# LIDO-HW_200_MCU_Peripherals_1.net
KiCad netlist of a schematic drawn in Altium Designer
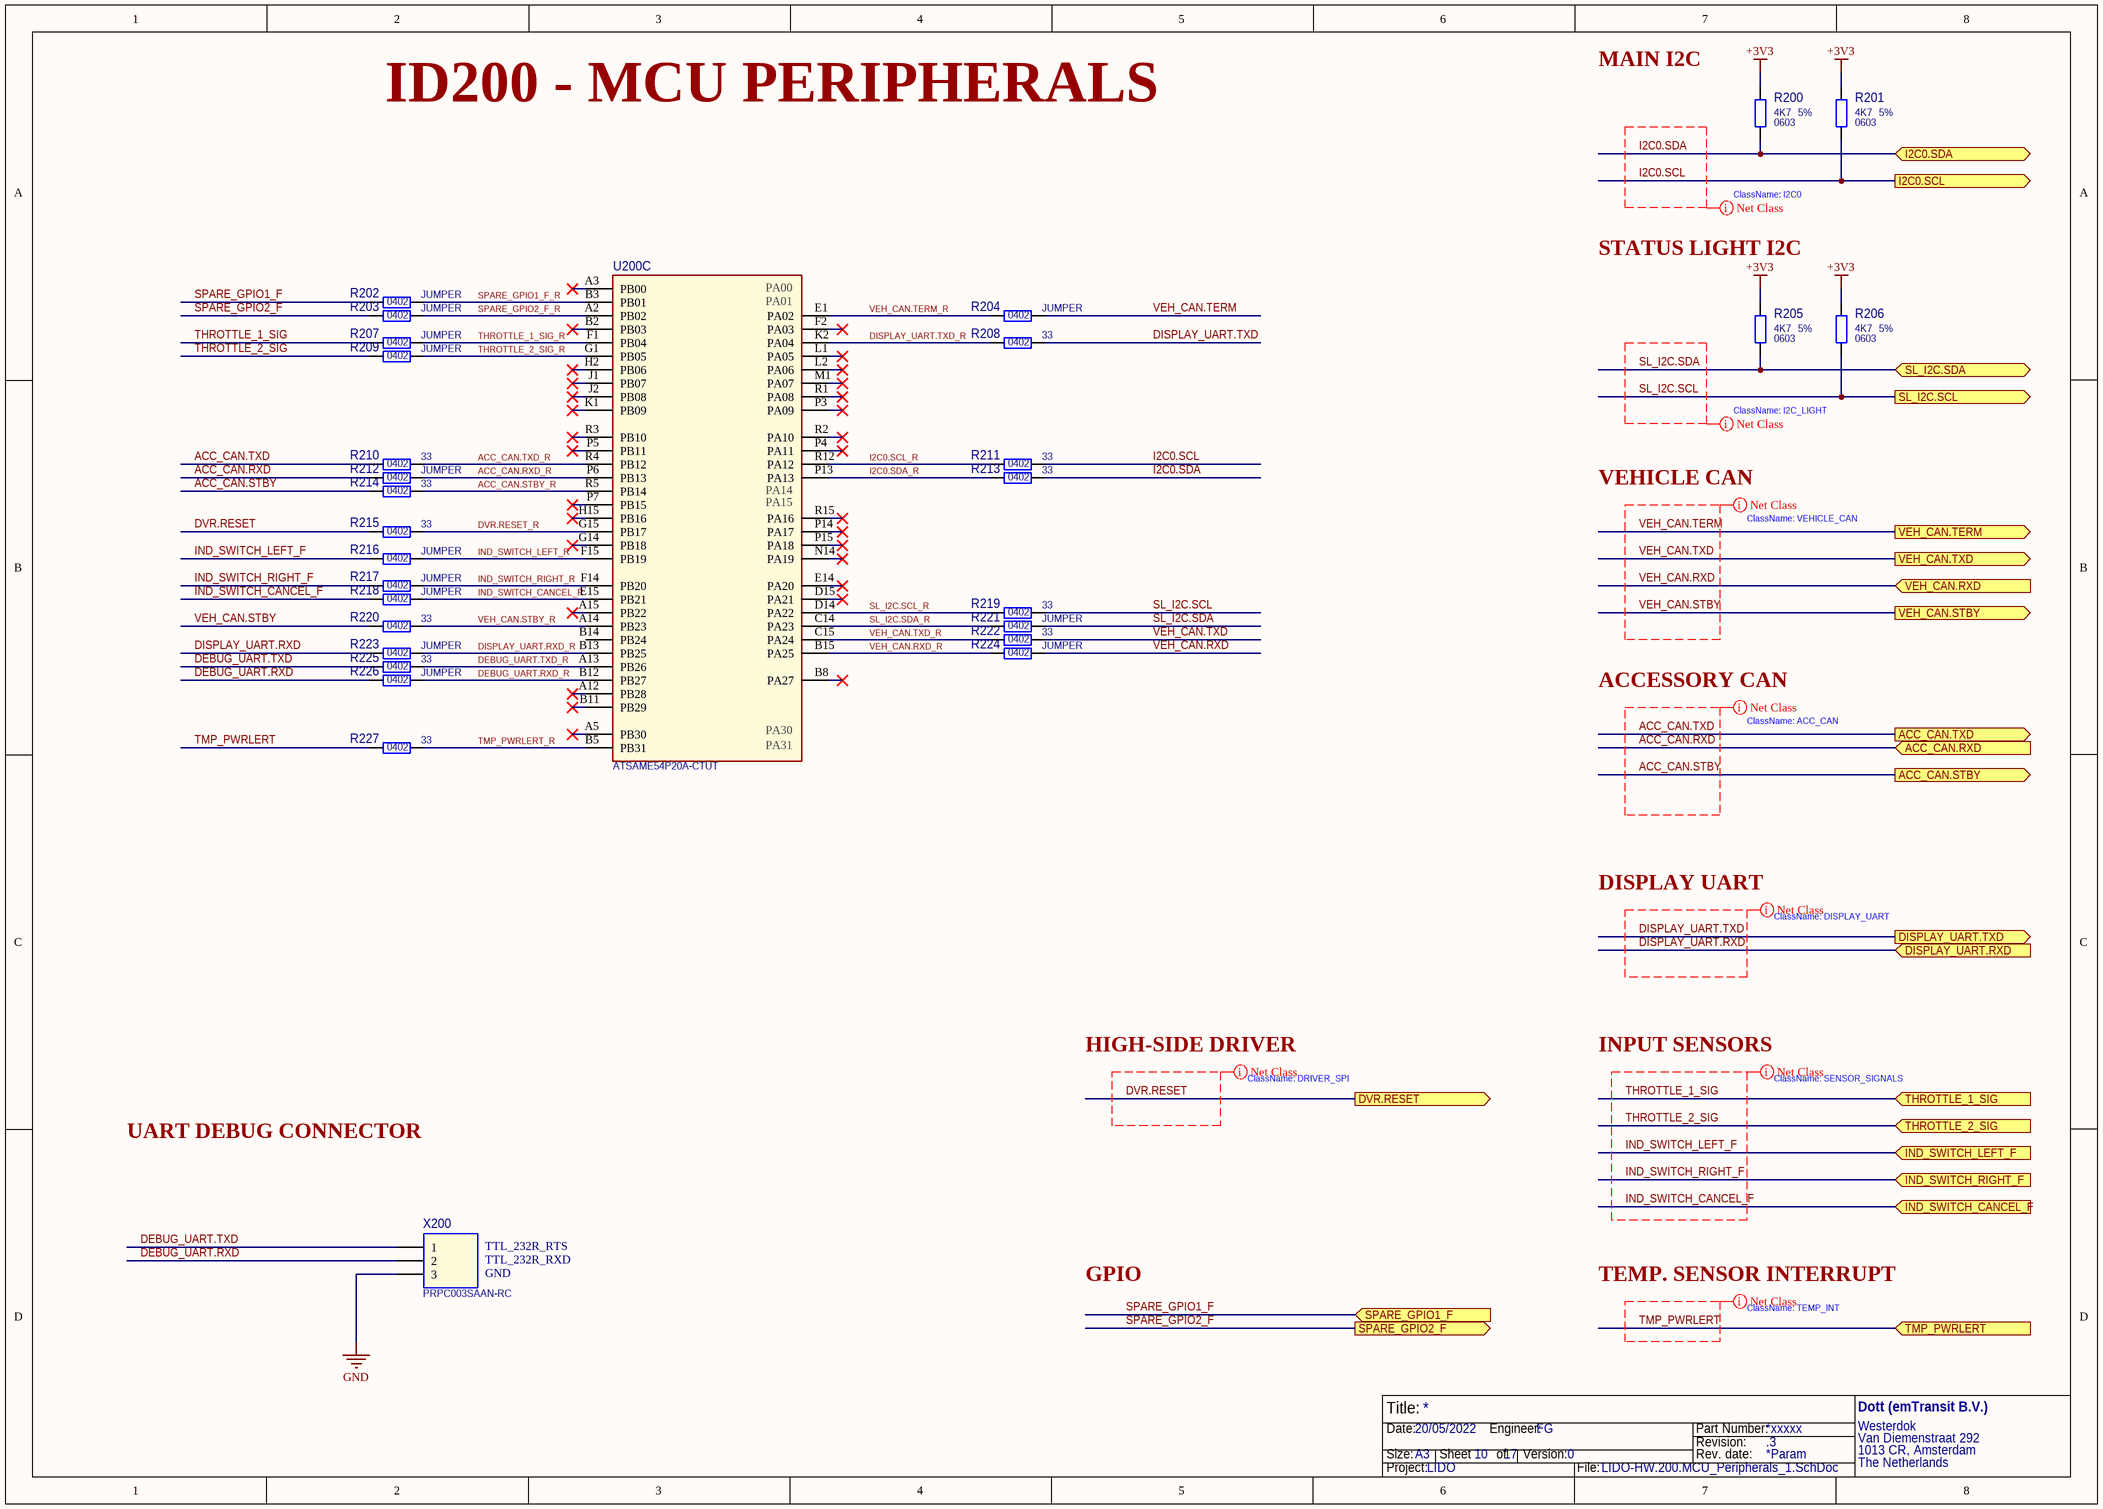
[diagram p0: LIDO-HW.200.MCU_Peripherals_1.SchDoc]

(export (version "E")
  (design (tool "Eeschema 10.0.6"))
  (components
    (comp (ref "R200")
      (value "4K7")
      (footprint "RES_0603_1608X60-N_YAGEO_A")
      (description "RES 4.7K OHM 5% 1/10W 0603")
      (fields
        (field (name "MANUFACTURER PART NUMBER") "RC0603JR-074K7L")
        (field (name "MANUFACTURER") "YAGEO")
        (field (name "PART VALUE 2") "5%")
        (field (name "PART PACKAGE") "0603")
      )
      (libsource (lib "") (part "Resistor_1"))
    )
    (comp (ref "R201")
      (value "4K7")
      (footprint "RES_0603_1608X60-N_YAGEO_A")
      (description "RES 4.7K OHM 5% 1/10W 0603")
      (fields
        (field (name "MANUFACTURER PART NUMBER") "RC0603JR-074K7L")
        (field (name "MANUFACTURER") "YAGEO")
        (field (name "PART VALUE 2") "5%")
        (field (name "PART PACKAGE") "0603")
      )
      (libsource (lib "") (part "Resistor_1"))
    )
    (comp (ref "R202")
      (value "JUMPER")
      (footprint "RES_0402_1005X40-N_YAGEO_A")
      (description "RES SMD 0 OHM JUMPER 1/10W 0402")
      (fields
        (field (name "MANUFACTURER PART NUMBER") "ERJ-2GE0R00X")
        (field (name "MANUFACTURER") "Panasonic Electronic Components")
        (field (name "PART PACKAGE") "0402")
      )
      (libsource (lib "DB_Library") (part "Resistor"))
    )
    (comp (ref "R203")
      (value "JUMPER")
      (footprint "RES_0402_1005X40-N_YAGEO_A")
      (description "RES SMD 0 OHM JUMPER 1/10W 0402")
      (fields
        (field (name "MANUFACTURER PART NUMBER") "ERJ-2GE0R00X")
        (field (name "MANUFACTURER") "Panasonic Electronic Components")
        (field (name "PART PACKAGE") "0402")
      )
      (libsource (lib "DB_Library") (part "Resistor"))
    )
    (comp (ref "R204")
      (value "JUMPER")
      (footprint "RES_0402_1005X40-N_YAGEO_A")
      (description "RES SMD 0 OHM JUMPER 1/10W 0402")
      (fields
        (field (name "MANUFACTURER PART NUMBER") "ERJ-2GE0R00X")
        (field (name "MANUFACTURER") "Panasonic Electronic Components")
        (field (name "PART PACKAGE") "0402")
      )
      (libsource (lib "DB_Library") (part "Resistor"))
    )
    (comp (ref "R205")
      (value "4K7")
      (footprint "RES_0603_1608X60-N_YAGEO_A")
      (description "RES 4.7K OHM 5% 1/10W 0603")
      (fields
        (field (name "MANUFACTURER PART NUMBER") "RC0603JR-074K7L")
        (field (name "MANUFACTURER") "YAGEO")
        (field (name "PART VALUE 2") "5%")
        (field (name "PART PACKAGE") "0603")
      )
      (libsource (lib "") (part "Resistor_1"))
    )
    (comp (ref "R206")
      (value "4K7")
      (footprint "RES_0603_1608X60-N_YAGEO_A")
      (description "RES 4.7K OHM 5% 1/10W 0603")
      (fields
        (field (name "MANUFACTURER PART NUMBER") "RC0603JR-074K7L")
        (field (name "MANUFACTURER") "YAGEO")
        (field (name "PART VALUE 2") "5%")
        (field (name "PART PACKAGE") "0603")
      )
      (libsource (lib "") (part "Resistor_1"))
    )
    (comp (ref "R207")
      (value "JUMPER")
      (footprint "RES_0402_1005X40-N_YAGEO_A")
      (description "RES SMD 0 OHM JUMPER 1/10W 0402")
      (fields
        (field (name "MANUFACTURER PART NUMBER") "ERJ-2GE0R00X")
        (field (name "MANUFACTURER") "Panasonic Electronic Components")
        (field (name "PART PACKAGE") "0402")
      )
      (libsource (lib "DB_Library") (part "Resistor"))
    )
    (comp (ref "R208")
      (value "33")
      (footprint "RES_0402_1005X40-N_YAGEO_A")
      (description "RES SMD 33 OHM 5% 1/10W 0402")
      (fields
        (field (name "MANUFACTURER PART NUMBER") "ERJ-2GEJ330X")
        (field (name "MANUFACTURER") "Panasonic Electronic Components")
        (field (name "PART PACKAGE") "0402")
      )
      (libsource (lib "DB_Library") (part "Resistor"))
    )
    (comp (ref "R209")
      (value "JUMPER")
      (footprint "RES_0402_1005X40-N_YAGEO_A")
      (description "RES SMD 0 OHM JUMPER 1/10W 0402")
      (fields
        (field (name "MANUFACTURER PART NUMBER") "ERJ-2GE0R00X")
        (field (name "MANUFACTURER") "Panasonic Electronic Components")
        (field (name "PART PACKAGE") "0402")
      )
      (libsource (lib "DB_Library") (part "Resistor"))
    )
    (comp (ref "R210")
      (value "33")
      (footprint "RES_0402_1005X40-N_YAGEO_A")
      (description "RES SMD 33 OHM 5% 1/10W 0402")
      (fields
        (field (name "MANUFACTURER PART NUMBER") "ERJ-2GEJ330X")
        (field (name "MANUFACTURER") "Panasonic Electronic Components")
        (field (name "PART PACKAGE") "0402")
      )
      (libsource (lib "DB_Library") (part "Resistor"))
    )
    (comp (ref "R211")
      (value "33")
      (footprint "RES_0402_1005X40-N_YAGEO_A")
      (description "RES SMD 33 OHM 5% 1/10W 0402")
      (fields
        (field (name "MANUFACTURER PART NUMBER") "ERJ-2GEJ330X")
        (field (name "MANUFACTURER") "Panasonic Electronic Components")
        (field (name "PART PACKAGE") "0402")
      )
      (libsource (lib "DB_Library") (part "Resistor"))
    )
    (comp (ref "R212")
      (value "JUMPER")
      (footprint "RES_0402_1005X40-N_YAGEO_A")
      (description "RES SMD 0 OHM JUMPER 1/10W 0402")
      (fields
        (field (name "MANUFACTURER PART NUMBER") "ERJ-2GE0R00X")
        (field (name "MANUFACTURER") "Panasonic Electronic Components")
        (field (name "PART PACKAGE") "0402")
      )
      (libsource (lib "DB_Library") (part "Resistor"))
    )
    (comp (ref "R213")
      (value "33")
      (footprint "RES_0402_1005X40-N_YAGEO_A")
      (description "RES SMD 33 OHM 5% 1/10W 0402")
      (fields
        (field (name "MANUFACTURER PART NUMBER") "ERJ-2GEJ330X")
        (field (name "MANUFACTURER") "Panasonic Electronic Components")
        (field (name "PART PACKAGE") "0402")
      )
      (libsource (lib "DB_Library") (part "Resistor"))
    )
    (comp (ref "R214")
      (value "33")
      (footprint "RES_0402_1005X40-N_YAGEO_A")
      (description "RES SMD 33 OHM 5% 1/10W 0402")
      (fields
        (field (name "MANUFACTURER PART NUMBER") "ERJ-2GEJ330X")
        (field (name "MANUFACTURER") "Panasonic Electronic Components")
        (field (name "PART PACKAGE") "0402")
      )
      (libsource (lib "DB_Library") (part "Resistor"))
    )
    (comp (ref "R215")
      (value "33")
      (footprint "RES_0402_1005X40-N_YAGEO_A")
      (description "RES SMD 33 OHM 5% 1/10W 0402")
      (fields
        (field (name "MANUFACTURER PART NUMBER") "ERJ-2GEJ330X")
        (field (name "MANUFACTURER") "Panasonic Electronic Components")
        (field (name "PART PACKAGE") "0402")
      )
      (libsource (lib "DB_Library") (part "Resistor"))
    )
    (comp (ref "R216")
      (value "JUMPER")
      (footprint "RES_0402_1005X40-N_YAGEO_A")
      (description "RES SMD 0 OHM JUMPER 1/10W 0402")
      (fields
        (field (name "MANUFACTURER PART NUMBER") "ERJ-2GE0R00X")
        (field (name "MANUFACTURER") "Panasonic Electronic Components")
        (field (name "PART PACKAGE") "0402")
      )
      (libsource (lib "DB_Library") (part "Resistor"))
    )
    (comp (ref "R217")
      (value "JUMPER")
      (footprint "RES_0402_1005X40-N_YAGEO_A")
      (description "RES SMD 0 OHM JUMPER 1/10W 0402")
      (fields
        (field (name "MANUFACTURER PART NUMBER") "ERJ-2GE0R00X")
        (field (name "MANUFACTURER") "Panasonic Electronic Components")
        (field (name "PART PACKAGE") "0402")
      )
      (libsource (lib "DB_Library") (part "Resistor"))
    )
    (comp (ref "R218")
      (value "JUMPER")
      (footprint "RES_0402_1005X40-N_YAGEO_A")
      (description "RES SMD 0 OHM JUMPER 1/10W 0402")
      (fields
        (field (name "MANUFACTURER PART NUMBER") "ERJ-2GE0R00X")
        (field (name "MANUFACTURER") "Panasonic Electronic Components")
        (field (name "PART PACKAGE") "0402")
      )
      (libsource (lib "DB_Library") (part "Resistor"))
    )
    (comp (ref "R219")
      (value "33")
      (footprint "RES_0402_1005X40-N_YAGEO_A")
      (description "RES SMD 33 OHM 5% 1/10W 0402")
      (fields
        (field (name "MANUFACTURER PART NUMBER") "ERJ-2GEJ330X")
        (field (name "MANUFACTURER") "Panasonic Electronic Components")
        (field (name "PART PACKAGE") "0402")
      )
      (libsource (lib "DB_Library") (part "Resistor"))
    )
    (comp (ref "R220")
      (value "33")
      (footprint "RES_0402_1005X40-N_YAGEO_A")
      (description "RES SMD 33 OHM 5% 1/10W 0402")
      (fields
        (field (name "MANUFACTURER PART NUMBER") "ERJ-2GEJ330X")
        (field (name "MANUFACTURER") "Panasonic Electronic Components")
        (field (name "PART PACKAGE") "0402")
      )
      (libsource (lib "DB_Library") (part "Resistor"))
    )
    (comp (ref "R221")
      (value "JUMPER")
      (footprint "RES_0402_1005X40-N_YAGEO_A")
      (description "RES SMD 0 OHM JUMPER 1/10W 0402")
      (fields
        (field (name "MANUFACTURER PART NUMBER") "ERJ-2GE0R00X")
        (field (name "MANUFACTURER") "Panasonic Electronic Components")
        (field (name "PART PACKAGE") "0402")
      )
      (libsource (lib "DB_Library") (part "Resistor"))
    )
    (comp (ref "R222")
      (value "33")
      (footprint "RES_0402_1005X40-N_YAGEO_A")
      (description "RES SMD 33 OHM 5% 1/10W 0402")
      (fields
        (field (name "MANUFACTURER PART NUMBER") "ERJ-2GEJ330X")
        (field (name "MANUFACTURER") "Panasonic Electronic Components")
        (field (name "PART PACKAGE") "0402")
      )
      (libsource (lib "DB_Library") (part "Resistor"))
    )
    (comp (ref "R223")
      (value "JUMPER")
      (footprint "RES_0402_1005X40-N_YAGEO_A")
      (description "RES SMD 0 OHM JUMPER 1/10W 0402")
      (fields
        (field (name "MANUFACTURER PART NUMBER") "ERJ-2GE0R00X")
        (field (name "MANUFACTURER") "Panasonic Electronic Components")
        (field (name "PART PACKAGE") "0402")
      )
      (libsource (lib "DB_Library") (part "Resistor"))
    )
    (comp (ref "R224")
      (value "JUMPER")
      (footprint "RES_0402_1005X40-N_YAGEO_A")
      (description "RES SMD 0 OHM JUMPER 1/10W 0402")
      (fields
        (field (name "MANUFACTURER PART NUMBER") "ERJ-2GE0R00X")
        (field (name "MANUFACTURER") "Panasonic Electronic Components")
        (field (name "PART PACKAGE") "0402")
      )
      (libsource (lib "DB_Library") (part "Resistor"))
    )
    (comp (ref "R225")
      (value "33")
      (footprint "RES_0402_1005X40-N_YAGEO_A")
      (description "RES SMD 33 OHM 5% 1/10W 0402")
      (fields
        (field (name "MANUFACTURER PART NUMBER") "ERJ-2GEJ330X")
        (field (name "MANUFACTURER") "Panasonic Electronic Components")
        (field (name "PART PACKAGE") "0402")
      )
      (libsource (lib "DB_Library") (part "Resistor"))
    )
    (comp (ref "R226")
      (value "JUMPER")
      (footprint "RES_0402_1005X40-N_YAGEO_A")
      (description "RES SMD 0 OHM JUMPER 1/10W 0402")
      (fields
        (field (name "MANUFACTURER PART NUMBER") "ERJ-2GE0R00X")
        (field (name "MANUFACTURER") "Panasonic Electronic Components")
        (field (name "PART PACKAGE") "0402")
      )
      (libsource (lib "DB_Library") (part "Resistor"))
    )
    (comp (ref "R227")
      (value "33")
      (footprint "RES_0402_1005X40-N_YAGEO_A")
      (description "RES SMD 33 OHM 5% 1/10W 0402")
      (fields
        (field (name "MANUFACTURER PART NUMBER") "ERJ-2GEJ330X")
        (field (name "MANUFACTURER") "Panasonic Electronic Components")
        (field (name "PART PACKAGE") "0402")
      )
      (libsource (lib "DB_Library") (part "Resistor"))
    )
    (comp (ref "U200")
      (value "ATSAME54P20A-CTUT")
      (footprint "BGA120CP50_15X15_800X800X120B25-N_MICROCHIP_A")
      (fields (field (name "MANUFACTURER") "Microchip Technology") (field (name "OBSOLETE PART") "False"))
      (libsource (lib "DB_Library") (part "ATMEL_ATSAME54P20A-CT_A"))
    )
    (comp (ref "X200")
      (value "PRPC003SAAN-RC")
      (footprint "HDR_3POS_1X3-N_WURTH_A")
      (description "CONN HEADER VERT 3POS 2.54MM")
      (fields
        (field (name "MANUFACTURER") "Sullins Connector Solutions")
        (field (name "OBSOLETE PART") "False")
      )
      (libsource (lib "DB_Library") (part "RECT_3PIN_1R_A"))
    )
  )
  (nets
    (net (code "1") (name "+3V3") (class "Default")
      (node (ref "R200") (pin "2") (pinfunction "2_2") (pintype "passive"))
      (node (ref "R201") (pin "2") (pinfunction "2_2") (pintype "passive"))
      (node (ref "R205") (pin "2") (pinfunction "2_2") (pintype "passive"))
      (node (ref "R206") (pin "2") (pinfunction "2_2") (pintype "passive"))
    )
    (net (code "2") (name "/ACC_CAN.RXD") (class "Default")
      (node (ref "R212") (pin "1") (pinfunction "1_1") (pintype "passive"))
    )
    (net (code "3") (name "/ACC_CAN.RXD_R") (class "Default")
      (node (ref "R212") (pin "2") (pinfunction "2_2") (pintype "passive"))
      (node (ref "U200") (pin "P6") (pinfunction "PB13_P6") (pintype "passive"))
    )
    (net (code "4") (name "/ACC_CAN.STBY") (class "Default")
      (node (ref "R214") (pin "1") (pinfunction "1_1") (pintype "passive"))
    )
    (net (code "5") (name "/ACC_CAN.STBY_R") (class "Default")
      (node (ref "R214") (pin "2") (pinfunction "2_2") (pintype "passive"))
      (node (ref "U200") (pin "R5") (pinfunction "PB14_R5") (pintype "passive"))
    )
    (net (code "6") (name "/ACC_CAN.TXD") (class "Default")
      (node (ref "R210") (pin "1") (pinfunction "1_1") (pintype "passive"))
    )
    (net (code "7") (name "/ACC_CAN.TXD_R") (class "Default")
      (node (ref "R210") (pin "2") (pinfunction "2_2") (pintype "passive"))
      (node (ref "U200") (pin "R4") (pinfunction "PB12_R4") (pintype "passive"))
    )
    (net (code "8") (name "/DEBUG_UART.RXD") (class "Default")
      (node (ref "R226") (pin "1") (pinfunction "1_1") (pintype "passive"))
      (node (ref "X200") (pin "2") (pinfunction "2_2") (pintype "passive"))
    )
    (net (code "9") (name "/DEBUG_UART.RXD_R") (class "Default")
      (node (ref "R226") (pin "2") (pinfunction "2_2") (pintype "passive"))
      (node (ref "U200") (pin "B12") (pinfunction "PB27_B12") (pintype "passive"))
    )
    (net (code "10") (name "/DEBUG_UART.TXD") (class "Default")
      (node (ref "R225") (pin "1") (pinfunction "1_1") (pintype "passive"))
      (node (ref "X200") (pin "1") (pinfunction "1_1") (pintype "passive"))
    )
    (net (code "11") (name "/DEBUG_UART.TXD_R") (class "Default")
      (node (ref "R225") (pin "2") (pinfunction "2_2") (pintype "passive"))
      (node (ref "U200") (pin "A13") (pinfunction "PB26_A13") (pintype "passive"))
    )
    (net (code "12") (name "/DISPLAY_UART.RXD") (class "Default")
      (node (ref "R223") (pin "1") (pinfunction "1_1") (pintype "passive"))
    )
    (net (code "13") (name "/DISPLAY_UART.RXD_R") (class "Default")
      (node (ref "R223") (pin "2") (pinfunction "2_2") (pintype "passive"))
      (node (ref "U200") (pin "B13") (pinfunction "PB25_B13") (pintype "passive"))
    )
    (net (code "14") (name "/DISPLAY_UART.TXD") (class "Default")
      (node (ref "R208") (pin "2") (pinfunction "2_2") (pintype "passive"))
    )
    (net (code "15") (name "/DISPLAY_UART.TXD_R") (class "Default")
      (node (ref "R208") (pin "1") (pinfunction "1_1") (pintype "passive"))
      (node (ref "U200") (pin "K2") (pinfunction "PA04_K2") (pintype "passive"))
    )
    (net (code "16") (name "/DVR.RESET") (class "Default")
      (node (ref "R215") (pin "1") (pinfunction "1_1") (pintype "passive"))
    )
    (net (code "17") (name "/DVR.RESET_R") (class "Default")
      (node (ref "R215") (pin "2") (pinfunction "2_2") (pintype "passive"))
      (node (ref "U200") (pin "G15") (pinfunction "PB17_G15") (pintype "passive"))
    )
    (net (code "18") (name "/I2C0.SCL") (class "Default")
      (node (ref "R201") (pin "1") (pinfunction "1_1") (pintype "passive"))
      (node (ref "R211") (pin "2") (pinfunction "2_2") (pintype "passive"))
    )
    (net (code "19") (name "/I2C0.SCL_R") (class "Default")
      (node (ref "R211") (pin "1") (pinfunction "1_1") (pintype "passive"))
      (node (ref "U200") (pin "R12") (pinfunction "PA12_R12") (pintype "passive"))
    )
    (net (code "20") (name "/I2C0.SDA") (class "Default")
      (node (ref "R200") (pin "1") (pinfunction "1_1") (pintype "passive"))
      (node (ref "R213") (pin "2") (pinfunction "2_2") (pintype "passive"))
    )
    (net (code "21") (name "/I2C0.SDA_R") (class "Default")
      (node (ref "R213") (pin "1") (pinfunction "1_1") (pintype "passive"))
      (node (ref "U200") (pin "P13") (pinfunction "PA13_P13") (pintype "passive"))
    )
    (net (code "22") (name "/IND_SWITCH_CANCEL_F") (class "Default")
      (node (ref "R218") (pin "1") (pinfunction "1_1") (pintype "passive"))
    )
    (net (code "23") (name "/IND_SWITCH_CANCEL_R") (class "Default")
      (node (ref "R218") (pin "2") (pinfunction "2_2") (pintype "passive"))
      (node (ref "U200") (pin "E15") (pinfunction "PB21_E15") (pintype "passive"))
    )
    (net (code "24") (name "/IND_SWITCH_LEFT_F") (class "Default")
      (node (ref "R216") (pin "1") (pinfunction "1_1") (pintype "passive"))
    )
    (net (code "25") (name "/IND_SWITCH_LEFT_R") (class "Default")
      (node (ref "R216") (pin "2") (pinfunction "2_2") (pintype "passive"))
      (node (ref "U200") (pin "F15") (pinfunction "PB19_F15") (pintype "passive"))
    )
    (net (code "26") (name "/IND_SWITCH_RIGHT_F") (class "Default")
      (node (ref "R217") (pin "1") (pinfunction "1_1") (pintype "passive"))
    )
    (net (code "27") (name "/IND_SWITCH_RIGHT_R") (class "Default")
      (node (ref "R217") (pin "2") (pinfunction "2_2") (pintype "passive"))
      (node (ref "U200") (pin "F14") (pinfunction "PB20_F14") (pintype "passive"))
    )
    (net (code "28") (name "/SL_I2C.SCL") (class "Default")
      (node (ref "R206") (pin "1") (pinfunction "1_1") (pintype "passive"))
      (node (ref "R219") (pin "2") (pinfunction "2_2") (pintype "passive"))
    )
    (net (code "29") (name "/SL_I2C.SCL_R") (class "Default")
      (node (ref "R219") (pin "1") (pinfunction "1_1") (pintype "passive"))
      (node (ref "U200") (pin "D14") (pinfunction "PA22_D14") (pintype "passive"))
    )
    (net (code "30") (name "/SL_I2C.SDA") (class "Default")
      (node (ref "R205") (pin "1") (pinfunction "1_1") (pintype "passive"))
      (node (ref "R221") (pin "2") (pinfunction "2_2") (pintype "passive"))
    )
    (net (code "31") (name "/SL_I2C.SDA_R") (class "Default")
      (node (ref "R221") (pin "1") (pinfunction "1_1") (pintype "passive"))
      (node (ref "U200") (pin "C14") (pinfunction "PA23_C14") (pintype "passive"))
    )
    (net (code "32") (name "/SPARE_GPIO1_F") (class "Default")
      (node (ref "R202") (pin "1") (pinfunction "1_1") (pintype "passive"))
    )
    (net (code "33") (name "/SPARE_GPIO1_F_R") (class "Default")
      (node (ref "R202") (pin "2") (pinfunction "2_2") (pintype "passive"))
      (node (ref "U200") (pin "B3") (pinfunction "PB01_B3") (pintype "passive"))
    )
    (net (code "34") (name "/SPARE_GPIO2_F") (class "Default")
      (node (ref "R203") (pin "1") (pinfunction "1_1") (pintype "passive"))
    )
    (net (code "35") (name "/SPARE_GPIO2_F_R") (class "Default")
      (node (ref "R203") (pin "2") (pinfunction "2_2") (pintype "passive"))
      (node (ref "U200") (pin "A2") (pinfunction "PB02_A2") (pintype "passive"))
    )
    (net (code "36") (name "/THROTTLE_1_SIG") (class "Default")
      (node (ref "R207") (pin "1") (pinfunction "1_1") (pintype "passive"))
    )
    (net (code "37") (name "/THROTTLE_1_SIG_R") (class "Default")
      (node (ref "R207") (pin "2") (pinfunction "2_2") (pintype "passive"))
      (node (ref "U200") (pin "F1") (pinfunction "PB04_F1") (pintype "passive"))
    )
    (net (code "38") (name "/THROTTLE_2_SIG") (class "Default")
      (node (ref "R209") (pin "1") (pinfunction "1_1") (pintype "passive"))
    )
    (net (code "39") (name "/THROTTLE_2_SIG_R") (class "Default")
      (node (ref "R209") (pin "2") (pinfunction "2_2") (pintype "passive"))
      (node (ref "U200") (pin "G1") (pinfunction "PB05_G1") (pintype "passive"))
    )
    (net (code "40") (name "/TMP_PWRLERT") (class "Default")
      (node (ref "R227") (pin "1") (pinfunction "1_1") (pintype "passive"))
    )
    (net (code "41") (name "/TMP_PWRLERT_R") (class "Default")
      (node (ref "R227") (pin "2") (pinfunction "2_2") (pintype "passive"))
      (node (ref "U200") (pin "B5") (pinfunction "PB31_B5") (pintype "passive"))
    )
    (net (code "42") (name "/VEH_CAN.RXD") (class "Default")
      (node (ref "R224") (pin "2") (pinfunction "2_2") (pintype "passive"))
    )
    (net (code "43") (name "/VEH_CAN.RXD_R") (class "Default")
      (node (ref "R224") (pin "1") (pinfunction "1_1") (pintype "passive"))
      (node (ref "U200") (pin "B15") (pinfunction "PA25_B15") (pintype "passive"))
    )
    (net (code "44") (name "/VEH_CAN.STBY") (class "Default")
      (node (ref "R220") (pin "1") (pinfunction "1_1") (pintype "passive"))
    )
    (net (code "45") (name "/VEH_CAN.STBY_R") (class "Default")
      (node (ref "R220") (pin "2") (pinfunction "2_2") (pintype "passive"))
      (node (ref "U200") (pin "A14") (pinfunction "PB23_A14") (pintype "passive"))
    )
    (net (code "46") (name "/VEH_CAN.TERM") (class "Default")
      (node (ref "R204") (pin "2") (pinfunction "2_2") (pintype "passive"))
    )
    (net (code "47") (name "/VEH_CAN.TERM_R") (class "Default")
      (node (ref "R204") (pin "1") (pinfunction "1_1") (pintype "passive"))
      (node (ref "U200") (pin "E1") (pinfunction "PA02_E1") (pintype "passive"))
    )
    (net (code "48") (name "/VEH_CAN.TXD") (class "Default")
      (node (ref "R222") (pin "2") (pinfunction "2_2") (pintype "passive"))
    )
    (net (code "49") (name "/VEH_CAN.TXD_R") (class "Default")
      (node (ref "R222") (pin "1") (pinfunction "1_1") (pintype "passive"))
      (node (ref "U200") (pin "C15") (pinfunction "PA24_C15") (pintype "passive"))
    )
    (net (code "50") (name "GND") (class "Default")
      (node (ref "X200") (pin "3") (pinfunction "3_3") (pintype "passive"))
    )
    (net (code "51") (name "unconnected-(U200C-PA03-PadF2)") (class "Default")
      (node (ref "U200") (pin "F2") (pinfunction "PA03_F2") (pintype "passive+no_connect"))
    )
    (net (code "52") (name "unconnected-(U200C-PA05-PadL1)") (class "Default")
      (node (ref "U200") (pin "L1") (pinfunction "PA05_L1") (pintype "passive+no_connect"))
    )
    (net (code "53") (name "unconnected-(U200C-PA06-PadL2)") (class "Default")
      (node (ref "U200") (pin "L2") (pinfunction "PA06_L2") (pintype "passive+no_connect"))
    )
    (net (code "54") (name "unconnected-(U200C-PA07-PadM1)") (class "Default")
      (node (ref "U200") (pin "M1") (pinfunction "PA07_M1") (pintype "passive+no_connect"))
    )
    (net (code "55") (name "unconnected-(U200C-PA08-PadR1)") (class "Default")
      (node (ref "U200") (pin "R1") (pinfunction "PA08_R1") (pintype "passive+no_connect"))
    )
    (net (code "56") (name "unconnected-(U200C-PA09-PadP3)") (class "Default")
      (node (ref "U200") (pin "P3") (pinfunction "PA09_P3") (pintype "passive+no_connect"))
    )
    (net (code "57") (name "unconnected-(U200C-PA10-PadR2)") (class "Default")
      (node (ref "U200") (pin "R2") (pinfunction "PA10_R2") (pintype "passive+no_connect"))
    )
    (net (code "58") (name "unconnected-(U200C-PA11-PadP4)") (class "Default")
      (node (ref "U200") (pin "P4") (pinfunction "PA11_P4") (pintype "passive+no_connect"))
    )
    (net (code "59") (name "unconnected-(U200C-PA16-PadR15)") (class "Default")
      (node (ref "U200") (pin "R15") (pinfunction "PA16_R15") (pintype "passive+no_connect"))
    )
    (net (code "60") (name "unconnected-(U200C-PA17-PadP14)") (class "Default")
      (node (ref "U200") (pin "P14") (pinfunction "PA17_P14") (pintype "passive+no_connect"))
    )
    (net (code "61") (name "unconnected-(U200C-PA18-PadP15)") (class "Default")
      (node (ref "U200") (pin "P15") (pinfunction "PA18_P15") (pintype "passive+no_connect"))
    )
    (net (code "62") (name "unconnected-(U200C-PA19-PadN14)") (class "Default")
      (node (ref "U200") (pin "N14") (pinfunction "PA19_N14") (pintype "passive+no_connect"))
    )
    (net (code "63") (name "unconnected-(U200C-PA20-PadE14)") (class "Default")
      (node (ref "U200") (pin "E14") (pinfunction "PA20_E14") (pintype "passive+no_connect"))
    )
    (net (code "64") (name "unconnected-(U200C-PA21-PadD15)") (class "Default")
      (node (ref "U200") (pin "D15") (pinfunction "PA21_D15") (pintype "passive+no_connect"))
    )
    (net (code "65") (name "unconnected-(U200C-PA27-PadB8)") (class "Default")
      (node (ref "U200") (pin "B8") (pinfunction "PA27_B8") (pintype "passive+no_connect"))
    )
    (net (code "66") (name "unconnected-(U200C-PB00-PadA3)") (class "Default")
      (node (ref "U200") (pin "A3") (pinfunction "PB00_A3") (pintype "passive+no_connect"))
    )
    (net (code "67") (name "unconnected-(U200C-PB03-PadB2)") (class "Default")
      (node (ref "U200") (pin "B2") (pinfunction "PB03_B2") (pintype "passive+no_connect"))
    )
    (net (code "68") (name "unconnected-(U200C-PB06-PadH2)") (class "Default")
      (node (ref "U200") (pin "H2") (pinfunction "PB06_H2") (pintype "passive+no_connect"))
    )
    (net (code "69") (name "unconnected-(U200C-PB07-PadJ1)") (class "Default")
      (node (ref "U200") (pin "J1") (pinfunction "PB07_J1") (pintype "passive+no_connect"))
    )
    (net (code "70") (name "unconnected-(U200C-PB08-PadJ2)") (class "Default")
      (node (ref "U200") (pin "J2") (pinfunction "PB08_J2") (pintype "passive+no_connect"))
    )
    (net (code "71") (name "unconnected-(U200C-PB09-PadK1)") (class "Default")
      (node (ref "U200") (pin "K1") (pinfunction "PB09_K1") (pintype "passive+no_connect"))
    )
    (net (code "72") (name "unconnected-(U200C-PB10-PadR3)") (class "Default")
      (node (ref "U200") (pin "R3") (pinfunction "PB10_R3") (pintype "passive+no_connect"))
    )
    (net (code "73") (name "unconnected-(U200C-PB11-PadP5)") (class "Default")
      (node (ref "U200") (pin "P5") (pinfunction "PB11_P5") (pintype "passive+no_connect"))
    )
    (net (code "74") (name "unconnected-(U200C-PB15-PadP7)") (class "Default")
      (node (ref "U200") (pin "P7") (pinfunction "PB15_P7") (pintype "passive+no_connect"))
    )
    (net (code "75") (name "unconnected-(U200C-PB16-PadH15)") (class "Default")
      (node (ref "U200") (pin "H15") (pinfunction "PB16_H15") (pintype "passive+no_connect"))
    )
    (net (code "76") (name "unconnected-(U200C-PB18-PadG14)") (class "Default")
      (node (ref "U200") (pin "G14") (pinfunction "PB18_G14") (pintype "passive+no_connect"))
    )
    (net (code "77") (name "unconnected-(U200C-PB22-PadA15)") (class "Default")
      (node (ref "U200") (pin "A15") (pinfunction "PB22_A15") (pintype "passive+no_connect"))
    )
    (net (code "78") (name "unconnected-(U200C-PB24-PadB14)") (class "Default")
      (node (ref "U200") (pin "B14") (pinfunction "PB24_B14") (pintype "passive"))
    )
    (net (code "79") (name "unconnected-(U200C-PB28-PadA12)") (class "Default")
      (node (ref "U200") (pin "A12") (pinfunction "PB28_A12") (pintype "passive+no_connect"))
    )
    (net (code "80") (name "unconnected-(U200C-PB29-PadB11)") (class "Default")
      (node (ref "U200") (pin "B11") (pinfunction "PB29_B11") (pintype "passive+no_connect"))
    )
    (net (code "81") (name "unconnected-(U200C-PB30-PadA5)") (class "Default")
      (node (ref "U200") (pin "A5") (pinfunction "PB30_A5") (pintype "passive+no_connect"))
    )
  )
)
